# Mosfet_addon_Board.net
KiCad netlist of a schematic drawn in EAGLE
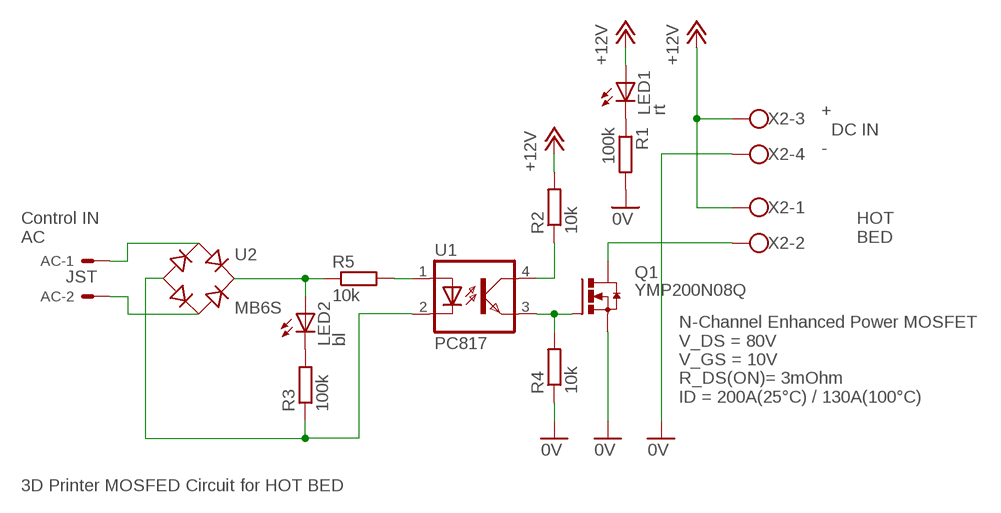
[diagram p0: schematic, sheet 1]

(export (version "E")
  (design (tool "Eeschema 10.0.6"))
  (components
    (comp (ref "AC")
      (value "JST")
      (footprint "eagle-import:JST-XH-02-PACKAGE-LONG-PAD")
      (libsource (lib "eagle-import") (part "JST-XH-02-PIN-LONG-PAD"))
    )
    (comp (ref "LED1")
      (value "rt")
      (footprint "eagle-import:CHIP-LED0805")
      (libsource (lib "eagle-import") (part "LEDCHIP-LED0805"))
    )
    (comp (ref "LED2")
      (value "bl")
      (footprint "eagle-import:CHIP-LED0805")
      (libsource (lib "eagle-import") (part "LEDCHIP-LED0805"))
    )
    (comp (ref "Q1")
      (value "YMP200N08Q")
      (footprint "eagle-import:TO247BV")
      (libsource (lib "eagle-import") (part "IRFP240"))
    )
    (comp (ref "R1")
      (value "100k")
      (footprint "eagle-import:R0805")
      (libsource (lib "eagle-import") (part "R-EU_R0805"))
    )
    (comp (ref "R2")
      (value "10k")
      (footprint "eagle-import:R0805")
      (libsource (lib "eagle-import") (part "R-EU_R0805"))
    )
    (comp (ref "R3")
      (value "100k")
      (footprint "eagle-import:R0805")
      (libsource (lib "eagle-import") (part "R-EU_R0805"))
    )
    (comp (ref "R4")
      (value "10k")
      (footprint "eagle-import:R0805")
      (libsource (lib "eagle-import") (part "R-EU_R0805"))
    )
    (comp (ref "R5")
      (value "10k")
      (footprint "eagle-import:R0805")
      (libsource (lib "eagle-import") (part "R-EU_R0805"))
    )
    (comp (ref "U1")
      (value "PC817")
      (footprint "eagle-import:DIL04")
      (fields (field (name "MPN") "PC817X4J000F"))
      (libsource (lib "eagle-import") (part "PC817"))
    )
    (comp (ref "U2")
      (value "MB6S")
      (footprint "eagle-import:SOIC-4")
      (libsource (lib "eagle-import") (part "MBS6"))
    )
    (comp (ref "X2")
      (value "W237-4")
      (footprint "eagle-import:W237-4")
      (libsource (lib "eagle-import") (part "W237-4"))
    )
  )
  (nets
    (net (code "1") (name "+12V") (class "Default")
      (node (ref "LED1") (pin "A") (pinfunction "A_A") (pintype "passive"))
      (node (ref "R2") (pin "2") (pinfunction "2_2") (pintype "passive"))
      (node (ref "X2") (pin "1") (pinfunction "KL_1") (pintype "passive"))
      (node (ref "X2") (pin "3") (pinfunction "KL_3") (pintype "passive"))
    )
    (net (code "2") (name "0V") (class "Default")
      (node (ref "Q1") (pin "S") (pinfunction "S_S") (pintype "passive"))
      (node (ref "R1") (pin "2") (pinfunction "2_2") (pintype "passive"))
      (node (ref "R4") (pin "1") (pinfunction "1_1") (pintype "passive"))
      (node (ref "X2") (pin "4") (pinfunction "KL_4") (pintype "passive"))
    )
    (net (code "3") (name "Net-(ACA-S)") (class "Default")
      (node (ref "AC") (pin "1") (pinfunction "S_1") (pintype "passive"))
      (node (ref "U2") (pin "~1") (pinfunction "AC1_~1") (pintype "passive"))
    )
    (net (code "4") (name "Net-(ACB-S)") (class "Default")
      (node (ref "AC") (pin "2") (pinfunction "S_2") (pintype "passive"))
      (node (ref "U2") (pin "~2") (pinfunction "AC2_~2") (pintype "passive"))
    )
    (net (code "5") (name "Net-(LED1-PadC)") (class "Default")
      (node (ref "LED1") (pin "C") (pinfunction "C_C") (pintype "passive"))
      (node (ref "R1") (pin "1") (pinfunction "1_1") (pintype "passive"))
    )
    (net (code "6") (name "Net-(LED2-PadA)") (class "Default")
      (node (ref "LED2") (pin "A") (pinfunction "A_A") (pintype "passive"))
      (node (ref "R5") (pin "1") (pinfunction "1_1") (pintype "passive"))
      (node (ref "U2") (pin "+") (pinfunction "+_+") (pintype "passive"))
    )
    (net (code "7") (name "Net-(LED2-PadC)") (class "Default")
      (node (ref "LED2") (pin "C") (pinfunction "C_C") (pintype "passive"))
      (node (ref "R3") (pin "2") (pinfunction "2_2") (pintype "passive"))
    )
    (net (code "8") (name "Net-(U1-A)") (class "Default")
      (node (ref "R5") (pin "2") (pinfunction "2_2") (pintype "passive"))
      (node (ref "U1") (pin "1") (pinfunction "A_1") (pintype "passive"))
    )
    (net (code "9") (name "Net-(U1-C)") (class "Default")
      (node (ref "R3") (pin "1") (pinfunction "1_1") (pintype "passive"))
      (node (ref "U1") (pin "2") (pinfunction "C_2") (pintype "passive"))
      (node (ref "U2") (pin "-") (pinfunction "-_-") (pintype "passive"))
    )
    (net (code "10") (name "Net-(U1-COL)") (class "Default")
      (node (ref "R2") (pin "1") (pinfunction "1_1") (pintype "passive"))
      (node (ref "U1") (pin "4") (pinfunction "COL_4") (pintype "passive"))
    )
    (net (code "11") (name "Net-(U1-EMIT)") (class "Default")
      (node (ref "Q1") (pin "G") (pinfunction "G_G") (pintype "passive"))
      (node (ref "R4") (pin "2") (pinfunction "2_2") (pintype "passive"))
      (node (ref "U1") (pin "3") (pinfunction "EMIT_3") (pintype "passive"))
    )
    (net (code "12") (name "Net-(X2B-KL)") (class "Default")
      (node (ref "Q1") (pin "D") (pinfunction "D_D") (pintype "passive"))
      (node (ref "X2") (pin "2") (pinfunction "KL_2") (pintype "passive"))
    )
  )
)
